# HapticVibrationShield.net
KiCad netlist of a schematic drawn in EAGLE
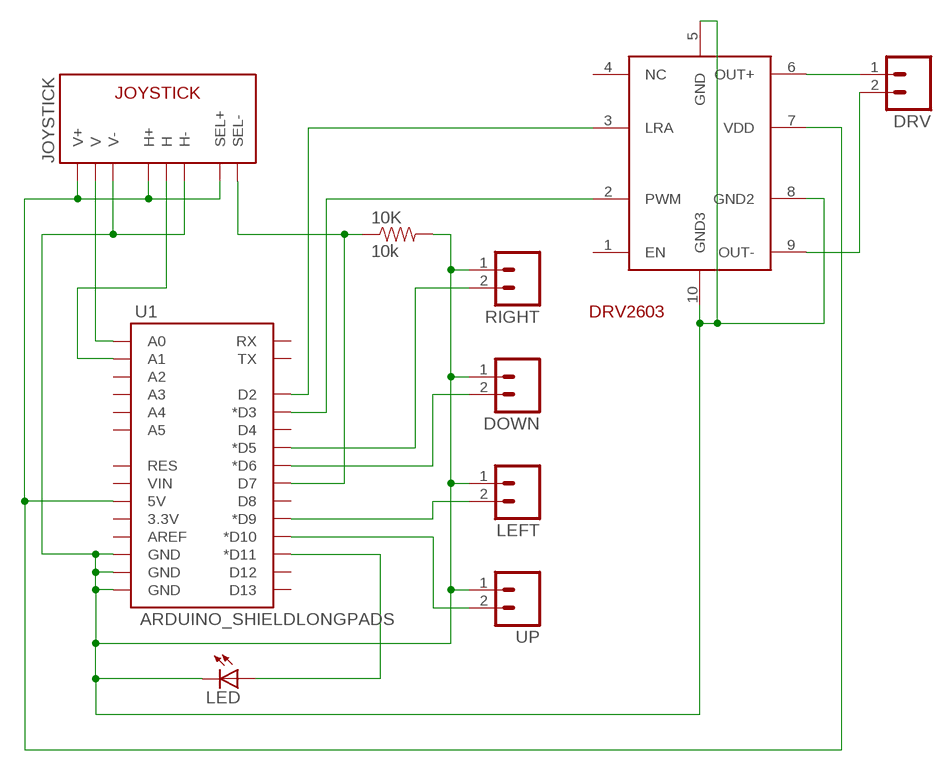
[diagram p0: schematic, sheet 1]

(export (version "E")
  (design (tool "Eeschema 10.0.6"))
  (components
    (comp (ref "10K")
      (value "10k")
      (footprint "eagle-import:R2010")
      (libsource (lib "eagle-import") (part "RESISTOR2010"))
    )
    (comp (ref "DOWN")
      (value "M02LOCK_LONGPADS")
      (footprint "eagle-import:1X02_LOCK_LONGPADS")
      (libsource (lib "eagle-import") (part "M02LOCK_LONGPADS"))
    )
    (comp (ref "DRV")
      (value "M02LOCK_LONGPADS")
      (footprint "eagle-import:1X02_LOCK_LONGPADS")
      (libsource (lib "eagle-import") (part "M02LOCK_LONGPADS"))
    )
    (comp (ref "DRV2603")
      (value "QFN-10QFN-10")
      (footprint "eagle-import:QFN-10")
      (libsource (lib "eagle-import") (part "QFN-10QFN-10"))
    )
    (comp (ref "JOYSTICK")
      (value "JOYSTICKPTH")
      (footprint "eagle-import:JOYSTICK")
      (libsource (lib "eagle-import") (part "JOYSTICKPTH"))
    )
    (comp (ref "LED")
      (value "LED5MM")
      (footprint "eagle-import:LED5MM")
      (libsource (lib "eagle-import") (part "LED5MM"))
    )
    (comp (ref "LEFT")
      (value "M02LOCK_LONGPADS")
      (footprint "eagle-import:1X02_LOCK_LONGPADS")
      (libsource (lib "eagle-import") (part "M02LOCK_LONGPADS"))
    )
    (comp (ref "RIGHT")
      (value "M02LOCK_LONGPADS")
      (footprint "eagle-import:1X02_LOCK_LONGPADS")
      (libsource (lib "eagle-import") (part "M02LOCK_LONGPADS"))
    )
    (comp (ref "U1")
      (value "ARDUINO_SHIELDLONGPADS")
      (footprint "eagle-import:DUEMILANOVE_SHIELD_LONGPADS")
      (libsource (lib "eagle-import") (part "ARDUINO_SHIELDLONGPADS"))
    )
    (comp (ref "UP")
      (value "M02LOCK_LONGPADS")
      (footprint "eagle-import:1X02_LOCK_LONGPADS")
      (libsource (lib "eagle-import") (part "M02LOCK_LONGPADS"))
    )
  )
  (nets
    (net (code "1") (name "Net-(DRV2603-GND)") (class "Default")
      (node (ref "10K") (pin "2") (pinfunction "2_2") (pintype "passive"))
      (node (ref "DOWN") (pin "1") (pinfunction "1_1") (pintype "passive"))
      (node (ref "DRV2603") (pin "10") (pinfunction "GND3_10") (pintype "bidirectional"))
      (node (ref "DRV2603") (pin "5") (pinfunction "GND_5") (pintype "bidirectional"))
      (node (ref "DRV2603") (pin "8") (pinfunction "GND2_8") (pintype "bidirectional"))
      (node (ref "JOYSTICK") (pin "H3") (pinfunction "H-_H3") (pintype "bidirectional"))
      (node (ref "JOYSTICK") (pin "V3") (pinfunction "V-_V3") (pintype "bidirectional"))
      (node (ref "LED") (pin "K") (pinfunction "C_K") (pintype "passive"))
      (node (ref "LEFT") (pin "1") (pinfunction "1_1") (pintype "passive"))
      (node (ref "RIGHT") (pin "1") (pinfunction "1_1") (pintype "passive"))
      (node (ref "U1") (pin "GND@0") (pinfunction "GND_GND@0") (pintype "bidirectional"))
      (node (ref "U1") (pin "GND@1") (pinfunction "GND_GND@1") (pintype "bidirectional"))
      (node (ref "U1") (pin "GND@2") (pinfunction "GND_GND@2") (pintype "bidirectional"))
      (node (ref "UP") (pin "1") (pinfunction "1_1") (pintype "passive"))
    )
    (net (code "2") (name "Net-(DRV2603-LRA)") (class "Default")
      (node (ref "DRV2603") (pin "3") (pinfunction "LRA_3") (pintype "bidirectional"))
      (node (ref "U1") (pin "D2") (pinfunction "D2_D2") (pintype "bidirectional"))
    )
    (net (code "3") (name "Net-(DRV2603-OUT+)") (class "Default")
      (node (ref "DRV") (pin "1") (pinfunction "1_1") (pintype "passive"))
      (node (ref "DRV2603") (pin "6") (pinfunction "OUT+_6") (pintype "bidirectional"))
    )
    (net (code "4") (name "Net-(DRV2603-OUT-)") (class "Default")
      (node (ref "DRV") (pin "2") (pinfunction "2_2") (pintype "passive"))
      (node (ref "DRV2603") (pin "9") (pinfunction "OUT-_9") (pintype "bidirectional"))
    )
    (net (code "5") (name "Net-(DRV2603-PWM)") (class "Default")
      (node (ref "DRV2603") (pin "2") (pinfunction "PWM_2") (pintype "bidirectional"))
      (node (ref "U1") (pin "D3") (pinfunction "*D3_D3") (pintype "bidirectional"))
    )
    (net (code "6") (name "Net-(DRV2603-VDD)") (class "Default")
      (node (ref "DRV2603") (pin "7") (pinfunction "VDD_7") (pintype "bidirectional"))
      (node (ref "JOYSTICK") (pin "B1A") (pinfunction "SEL+_B1A") (pintype "bidirectional"))
      (node (ref "JOYSTICK") (pin "H1") (pinfunction "H+_H1") (pintype "bidirectional"))
      (node (ref "JOYSTICK") (pin "V1") (pinfunction "V+_V1") (pintype "bidirectional"))
      (node (ref "U1") (pin "5V") (pinfunction "5V_5V") (pintype "bidirectional"))
    )
    (net (code "7") (name "Net-(JOYSTICK-H)") (class "Default")
      (node (ref "JOYSTICK") (pin "H2") (pinfunction "H_H2") (pintype "bidirectional"))
      (node (ref "U1") (pin "A1") (pinfunction "A1_A1") (pintype "bidirectional"))
    )
    (net (code "8") (name "Net-(JOYSTICK-SEL-)") (class "Default")
      (node (ref "10K") (pin "1") (pinfunction "1_1") (pintype "passive"))
      (node (ref "JOYSTICK") (pin "B2A") (pinfunction "SEL-_B2A") (pintype "bidirectional"))
      (node (ref "U1") (pin "D7") (pinfunction "D7_D7") (pintype "bidirectional"))
    )
    (net (code "9") (name "Net-(JOYSTICK-V)") (class "Default")
      (node (ref "JOYSTICK") (pin "V2") (pinfunction "V_V2") (pintype "bidirectional"))
      (node (ref "U1") (pin "A0") (pinfunction "A0_A0") (pintype "bidirectional"))
    )
    (net (code "10") (name "Net-(U1-*D5)") (class "Default")
      (node (ref "RIGHT") (pin "2") (pinfunction "2_2") (pintype "passive"))
      (node (ref "U1") (pin "D5") (pinfunction "*D5_D5") (pintype "bidirectional"))
    )
    (net (code "11") (name "Net-(U1-*D6)") (class "Default")
      (node (ref "DOWN") (pin "2") (pinfunction "2_2") (pintype "passive"))
      (node (ref "U1") (pin "D6") (pinfunction "*D6_D6") (pintype "bidirectional"))
    )
    (net (code "12") (name "Net-(U1-*D9)") (class "Default")
      (node (ref "LEFT") (pin "2") (pinfunction "2_2") (pintype "passive"))
      (node (ref "U1") (pin "D9") (pinfunction "*D9_D9") (pintype "bidirectional"))
    )
    (net (code "13") (name "Net-(U1-*D10)") (class "Default")
      (node (ref "U1") (pin "D10") (pinfunction "*D10_D10") (pintype "bidirectional"))
      (node (ref "UP") (pin "2") (pinfunction "2_2") (pintype "passive"))
    )
    (net (code "14") (name "Net-(U1-*D11)") (class "Default")
      (node (ref "LED") (pin "A") (pinfunction "A_A") (pintype "passive"))
      (node (ref "U1") (pin "D11") (pinfunction "*D11_D11") (pintype "bidirectional"))
    )
    (net (code "15") (name "unconnected-(DRV2603-EN-Pad1)") (class "Default")
      (node (ref "DRV2603") (pin "1") (pinfunction "EN_1") (pintype "bidirectional"))
    )
    (net (code "16") (name "unconnected-(DRV2603-NC-Pad4)") (class "Default")
      (node (ref "DRV2603") (pin "4") (pinfunction "NC_4") (pintype "bidirectional"))
    )
    (net (code "17") (name "unconnected-(U1-Pad3.3V)") (class "Default")
      (node (ref "U1") (pin "3.3V") (pinfunction "3.3V_3.3V") (pintype "bidirectional"))
    )
    (net (code "18") (name "unconnected-(U1-PadA2)") (class "Default")
      (node (ref "U1") (pin "A2") (pinfunction "A2_A2") (pintype "bidirectional"))
    )
    (net (code "19") (name "unconnected-(U1-PadA3)") (class "Default")
      (node (ref "U1") (pin "A3") (pinfunction "A3_A3") (pintype "bidirectional"))
    )
    (net (code "20") (name "unconnected-(U1-PadA4)") (class "Default")
      (node (ref "U1") (pin "A4") (pinfunction "A4_A4") (pintype "bidirectional"))
    )
    (net (code "21") (name "unconnected-(U1-PadA5)") (class "Default")
      (node (ref "U1") (pin "A5") (pinfunction "A5_A5") (pintype "bidirectional"))
    )
    (net (code "22") (name "unconnected-(U1-PadAREF)") (class "Default")
      (node (ref "U1") (pin "AREF") (pinfunction "AREF_AREF") (pintype "bidirectional"))
    )
    (net (code "23") (name "unconnected-(U1-PadD4)") (class "Default")
      (node (ref "U1") (pin "D4") (pinfunction "D4_D4") (pintype "bidirectional"))
    )
    (net (code "24") (name "unconnected-(U1-PadD8)") (class "Default")
      (node (ref "U1") (pin "D8") (pinfunction "D8_D8") (pintype "bidirectional"))
    )
    (net (code "25") (name "unconnected-(U1-PadD12)") (class "Default")
      (node (ref "U1") (pin "D12") (pinfunction "D12_D12") (pintype "bidirectional"))
    )
    (net (code "26") (name "unconnected-(U1-PadD13)") (class "Default")
      (node (ref "U1") (pin "D13") (pinfunction "D13_D13") (pintype "bidirectional"))
    )
    (net (code "27") (name "unconnected-(U1-PadRES)") (class "Default")
      (node (ref "U1") (pin "RES") (pinfunction "RES_RES") (pintype "bidirectional"))
    )
    (net (code "28") (name "unconnected-(U1-PadRX)") (class "Default")
      (node (ref "U1") (pin "RX") (pinfunction "RX_RX") (pintype "bidirectional"))
    )
    (net (code "29") (name "unconnected-(U1-PadTX)") (class "Default")
      (node (ref "U1") (pin "TX") (pinfunction "TX_TX") (pintype "bidirectional"))
    )
    (net (code "30") (name "unconnected-(U1-PadVIN)") (class "Default")
      (node (ref "U1") (pin "VIN") (pinfunction "VIN_VIN") (pintype "bidirectional"))
    )
  )
)
